# PowerKitPTH.net
KiCad netlist of a schematic drawn in EAGLE
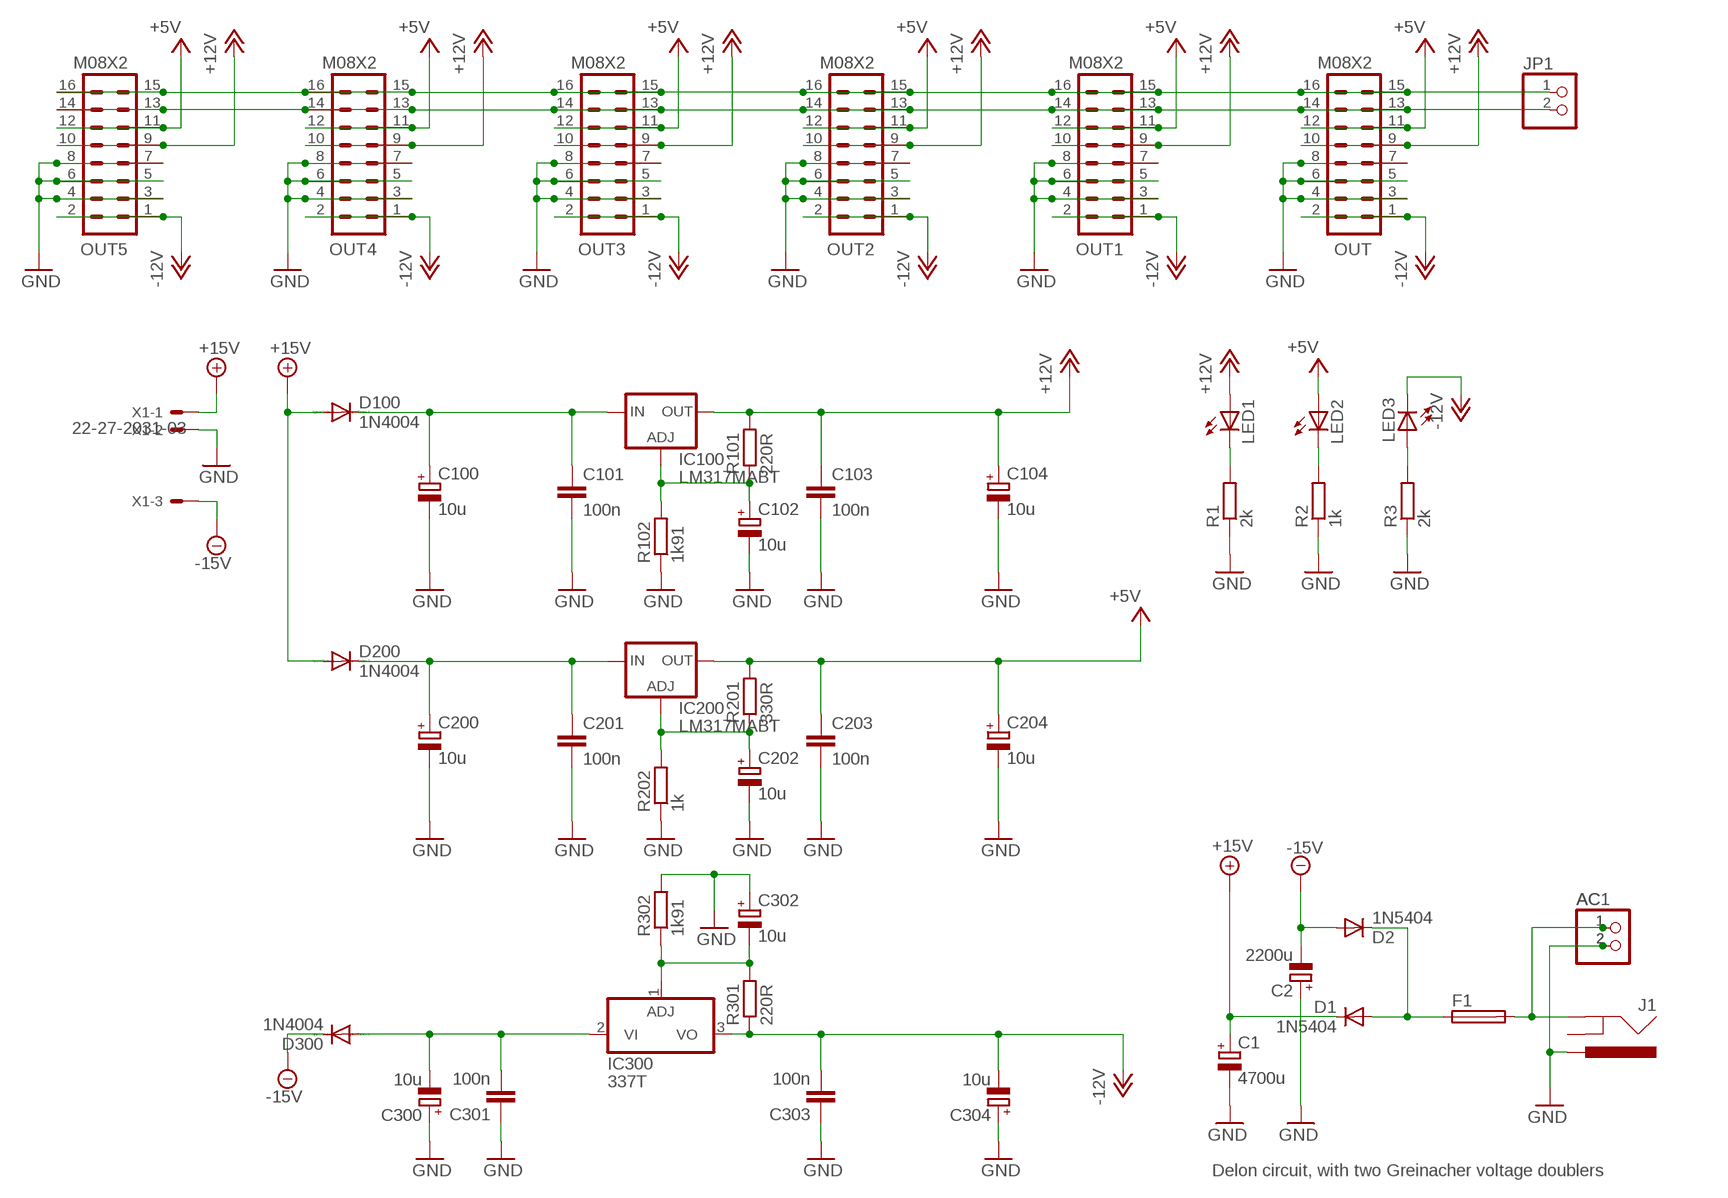
[diagram p0: schematic, sheet 1]

(export (version "E")
  (design (tool "Eeschema 10.0.6"))
  (components
    (comp (ref "AC")
      (value "PINHD-1X2")
      (footprint "eagle-import:1X02")
      (libsource (lib "eagle-import") (part "PINHD-1X2"))
    )
    (comp (ref "AC1")
      (value "PINHD-1X2")
      (footprint "eagle-import:1X02")
      (libsource (lib "eagle-import") (part "PINHD-1X2"))
    )
    (comp (ref "C1")
      (value "4700u")
      (footprint "eagle-import:E7,5-18")
      (libsource (lib "eagle-import") (part "resistor_CPOL-EUE7.5-18"))
    )
    (comp (ref "C2")
      (value "2200u")
      (footprint "eagle-import:E7,5-18")
      (libsource (lib "eagle-import") (part "resistor_CPOL-EUE7.5-18"))
    )
    (comp (ref "C100")
      (value "10u")
      (footprint "eagle-import:E2,5-6")
      (libsource (lib "eagle-import") (part "CPOL-EUE2.5-6"))
    )
    (comp (ref "C101")
      (value "100n")
      (footprint "eagle-import:C050-025X075")
      (libsource (lib "eagle-import") (part "C-EU050-025X075"))
    )
    (comp (ref "C102")
      (value "10u")
      (footprint "eagle-import:E2,5-6")
      (libsource (lib "eagle-import") (part "CPOL-EUE2.5-6"))
    )
    (comp (ref "C103")
      (value "100n")
      (footprint "eagle-import:C050-025X075")
      (libsource (lib "eagle-import") (part "C-EU050-025X075"))
    )
    (comp (ref "C104")
      (value "10u")
      (footprint "eagle-import:E2,5-6")
      (libsource (lib "eagle-import") (part "CPOL-EUE2.5-6"))
    )
    (comp (ref "C200")
      (value "10u")
      (footprint "eagle-import:E2,5-6")
      (libsource (lib "eagle-import") (part "CPOL-EUE2.5-6"))
    )
    (comp (ref "C201")
      (value "100n")
      (footprint "eagle-import:C050-025X075")
      (libsource (lib "eagle-import") (part "C-EU050-025X075"))
    )
    (comp (ref "C202")
      (value "10u")
      (footprint "eagle-import:E2,5-6")
      (libsource (lib "eagle-import") (part "CPOL-EUE2.5-6"))
    )
    (comp (ref "C203")
      (value "100n")
      (footprint "eagle-import:C050-025X075")
      (libsource (lib "eagle-import") (part "C-EU050-025X075"))
    )
    (comp (ref "C204")
      (value "10u")
      (footprint "eagle-import:E2,5-6")
      (libsource (lib "eagle-import") (part "CPOL-EUE2.5-6"))
    )
    (comp (ref "C300")
      (value "10u")
      (footprint "eagle-import:E2,5-6")
      (libsource (lib "eagle-import") (part "CPOL-EUE2.5-6"))
    )
    (comp (ref "C301")
      (value "100n")
      (footprint "eagle-import:C050-025X075")
      (libsource (lib "eagle-import") (part "C-EU050-025X075"))
    )
    (comp (ref "C302")
      (value "10u")
      (footprint "eagle-import:E2,5-6")
      (libsource (lib "eagle-import") (part "CPOL-EUE2.5-6"))
    )
    (comp (ref "C303")
      (value "100n")
      (footprint "eagle-import:C050-025X075")
      (libsource (lib "eagle-import") (part "C-EU050-025X075"))
    )
    (comp (ref "C304")
      (value "10u")
      (footprint "eagle-import:E2,5-6")
      (libsource (lib "eagle-import") (part "CPOL-EUE2.5-6"))
    )
    (comp (ref "D1")
      (value "1N5404")
      (footprint "eagle-import:DIODE-1N4001")
      (libsource (lib "eagle-import") (part "DIODE1N4001"))
    )
    (comp (ref "D2")
      (value "1N5404")
      (footprint "eagle-import:DIODE-1N4001")
      (libsource (lib "eagle-import") (part "DIODE1N4001"))
    )
    (comp (ref "D100")
      (value "1N4004")
      (footprint "eagle-import:DO41-10")
      (libsource (lib "eagle-import") (part "1N4004"))
    )
    (comp (ref "D200")
      (value "1N4004")
      (footprint "eagle-import:DO41-10")
      (libsource (lib "eagle-import") (part "1N4004"))
    )
    (comp (ref "D300")
      (value "1N4004")
      (footprint "eagle-import:DO41-10")
      (libsource (lib "eagle-import") (part "1N4004"))
    )
    (comp (ref "F1")
      (value "SH22,5")
      (footprint "eagle-import:SH22,5")
      (fields (field (name "MF") "SCHURTER") (field (name "MPN") "0031.8201"))
      (libsource (lib "eagle-import") (part "SH22,5"))
    )
    (comp (ref "IC100")
      (value "LM317MABT")
      (footprint "eagle-import:TO220L1")
      (libsource (lib "eagle-import") (part "LM317?MABT"))
    )
    (comp (ref "IC200")
      (value "LM317MABT")
      (footprint "eagle-import:TO220L1")
      (libsource (lib "eagle-import") (part "LM317?MABT"))
    )
    (comp (ref "IC300")
      (value "337T")
      (footprint "eagle-import:TO220H")
      (libsource (lib "eagle-import") (part "337T"))
    )
    (comp (ref "J1")
      (value "POWER_JACKPTH")
      (footprint "eagle-import:POWER_JACK_PTH")
      (libsource (lib "eagle-import") (part "POWER_JACKPTH"))
    )
    (comp (ref "JP1")
      (value "PINHD-1X2")
      (footprint "eagle-import:1X02")
      (libsource (lib "eagle-import") (part "PINHD-1X2"))
    )
    (comp (ref "LED1")
      (value "LED3MM")
      (footprint "eagle-import:LED3MM")
      (libsource (lib "eagle-import") (part "LED3MM"))
    )
    (comp (ref "LED2")
      (value "LED3MM")
      (footprint "eagle-import:LED3MM")
      (libsource (lib "eagle-import") (part "LED3MM"))
    )
    (comp (ref "LED3")
      (value "LED3MM")
      (footprint "eagle-import:LED3MM")
      (libsource (lib "eagle-import") (part "LED3MM"))
    )
    (comp (ref "OUT")
      (value "M08X2")
      (footprint "eagle-import:2X8")
      (libsource (lib "eagle-import") (part "M08X2"))
    )
    (comp (ref "OUT1")
      (value "M08X2")
      (footprint "eagle-import:2X8")
      (libsource (lib "eagle-import") (part "M08X2"))
    )
    (comp (ref "OUT2")
      (value "M08X2")
      (footprint "eagle-import:2X8")
      (libsource (lib "eagle-import") (part "M08X2"))
    )
    (comp (ref "OUT3")
      (value "M08X2")
      (footprint "eagle-import:2X8")
      (libsource (lib "eagle-import") (part "M08X2"))
    )
    (comp (ref "OUT4")
      (value "M08X2")
      (footprint "eagle-import:2X8")
      (libsource (lib "eagle-import") (part "M08X2"))
    )
    (comp (ref "OUT5")
      (value "M08X2")
      (footprint "eagle-import:2X8")
      (libsource (lib "eagle-import") (part "M08X2"))
    )
    (comp (ref "R1")
      (value "2k")
      (footprint "eagle-import:0204_7")
      (libsource (lib "eagle-import") (part "R-EU_0204/7"))
    )
    (comp (ref "R2")
      (value "1k")
      (footprint "eagle-import:0204_7")
      (libsource (lib "eagle-import") (part "R-EU_0204/7"))
    )
    (comp (ref "R3")
      (value "2k")
      (footprint "eagle-import:0204_7")
      (libsource (lib "eagle-import") (part "R-EU_0204/7"))
    )
    (comp (ref "R101")
      (value "220R")
      (footprint "eagle-import:0204_7")
      (libsource (lib "eagle-import") (part "R-EU_0204/7"))
    )
    (comp (ref "R102")
      (value "1k91")
      (footprint "eagle-import:0204_7")
      (libsource (lib "eagle-import") (part "R-EU_0204/7"))
    )
    (comp (ref "R201")
      (value "330R")
      (footprint "eagle-import:0204_7")
      (libsource (lib "eagle-import") (part "R-EU_0204/7"))
    )
    (comp (ref "R202")
      (value "1k")
      (footprint "eagle-import:0204_7")
      (libsource (lib "eagle-import") (part "R-EU_0204/7"))
    )
    (comp (ref "R301")
      (value "220R")
      (footprint "eagle-import:0204_7")
      (libsource (lib "eagle-import") (part "R-EU_0204/7"))
    )
    (comp (ref "R302")
      (value "1k91")
      (footprint "eagle-import:0204_7")
      (libsource (lib "eagle-import") (part "R-EU_0204/7"))
    )
    (comp (ref "X1")
      (value "22-27-2031-03")
      (footprint "eagle-import:6410-03")
      (libsource (lib "eagle-import") (part "22-?-0327-2031"))
    )
  )
  (nets
    (net (code "1") (name "+5V") (class "Default")
      (node (ref "C203") (pin "1") (pinfunction "1_1") (pintype "passive"))
      (node (ref "C204") (pin "+") (pinfunction "+_+") (pintype "passive"))
      (node (ref "IC200") (pin "2") (pinfunction "OUT_2") (pintype "passive"))
      (node (ref "LED2") (pin "A") (pinfunction "A_A") (pintype "passive"))
      (node (ref "OUT") (pin "11") (pinfunction "11_11") (pintype "passive"))
      (node (ref "OUT") (pin "12") (pinfunction "12_12") (pintype "passive"))
      (node (ref "OUT1") (pin "11") (pinfunction "11_11") (pintype "passive"))
      (node (ref "OUT1") (pin "12") (pinfunction "12_12") (pintype "passive"))
      (node (ref "OUT2") (pin "11") (pinfunction "11_11") (pintype "passive"))
      (node (ref "OUT2") (pin "12") (pinfunction "12_12") (pintype "passive"))
      (node (ref "OUT3") (pin "11") (pinfunction "11_11") (pintype "passive"))
      (node (ref "OUT3") (pin "12") (pinfunction "12_12") (pintype "passive"))
      (node (ref "OUT4") (pin "11") (pinfunction "11_11") (pintype "passive"))
      (node (ref "OUT4") (pin "12") (pinfunction "12_12") (pintype "passive"))
      (node (ref "OUT5") (pin "11") (pinfunction "11_11") (pintype "passive"))
      (node (ref "OUT5") (pin "12") (pinfunction "12_12") (pintype "passive"))
      (node (ref "R201") (pin "2") (pinfunction "2_2") (pintype "passive"))
    )
    (net (code "2") (name "+12V") (class "Default")
      (node (ref "C103") (pin "1") (pinfunction "1_1") (pintype "passive"))
      (node (ref "C104") (pin "+") (pinfunction "+_+") (pintype "passive"))
      (node (ref "IC100") (pin "2") (pinfunction "OUT_2") (pintype "passive"))
      (node (ref "LED1") (pin "A") (pinfunction "A_A") (pintype "passive"))
      (node (ref "OUT") (pin "10") (pinfunction "10_10") (pintype "passive"))
      (node (ref "OUT") (pin "9") (pinfunction "9_9") (pintype "passive"))
      (node (ref "OUT1") (pin "10") (pinfunction "10_10") (pintype "passive"))
      (node (ref "OUT1") (pin "9") (pinfunction "9_9") (pintype "passive"))
      (node (ref "OUT2") (pin "10") (pinfunction "10_10") (pintype "passive"))
      (node (ref "OUT2") (pin "9") (pinfunction "9_9") (pintype "passive"))
      (node (ref "OUT3") (pin "10") (pinfunction "10_10") (pintype "passive"))
      (node (ref "OUT3") (pin "9") (pinfunction "9_9") (pintype "passive"))
      (node (ref "OUT4") (pin "10") (pinfunction "10_10") (pintype "passive"))
      (node (ref "OUT4") (pin "9") (pinfunction "9_9") (pintype "passive"))
      (node (ref "OUT5") (pin "10") (pinfunction "10_10") (pintype "passive"))
      (node (ref "OUT5") (pin "9") (pinfunction "9_9") (pintype "passive"))
      (node (ref "R101") (pin "2") (pinfunction "2_2") (pintype "passive"))
    )
    (net (code "3") (name "+15V") (class "Default")
      (node (ref "C1") (pin "+") (pinfunction "+_+") (pintype "passive"))
      (node (ref "D1") (pin "C") (pinfunction "C_C") (pintype "passive"))
      (node (ref "D100") (pin "A") (pinfunction "A_A") (pintype "passive"))
      (node (ref "D200") (pin "A") (pinfunction "A_A") (pintype "passive"))
      (node (ref "X1") (pin "1") (pinfunction "S_1") (pintype "passive"))
    )
    (net (code "4") (name "-12V") (class "Default")
      (node (ref "C303") (pin "2") (pinfunction "2_2") (pintype "passive"))
      (node (ref "C304") (pin "-") (pinfunction "-_-") (pintype "passive"))
      (node (ref "IC300") (pin "3") (pinfunction "VO_3") (pintype "passive"))
      (node (ref "LED3") (pin "K") (pinfunction "C_K") (pintype "passive"))
      (node (ref "OUT") (pin "1") (pinfunction "1_1") (pintype "passive"))
      (node (ref "OUT") (pin "2") (pinfunction "2_2") (pintype "passive"))
      (node (ref "OUT1") (pin "1") (pinfunction "1_1") (pintype "passive"))
      (node (ref "OUT1") (pin "2") (pinfunction "2_2") (pintype "passive"))
      (node (ref "OUT2") (pin "1") (pinfunction "1_1") (pintype "passive"))
      (node (ref "OUT2") (pin "2") (pinfunction "2_2") (pintype "passive"))
      (node (ref "OUT3") (pin "1") (pinfunction "1_1") (pintype "passive"))
      (node (ref "OUT3") (pin "2") (pinfunction "2_2") (pintype "passive"))
      (node (ref "OUT4") (pin "1") (pinfunction "1_1") (pintype "passive"))
      (node (ref "OUT4") (pin "2") (pinfunction "2_2") (pintype "passive"))
      (node (ref "OUT5") (pin "1") (pinfunction "1_1") (pintype "passive"))
      (node (ref "OUT5") (pin "2") (pinfunction "2_2") (pintype "passive"))
      (node (ref "R301") (pin "1") (pinfunction "1_1") (pintype "passive"))
    )
    (net (code "5") (name "-15V") (class "Default")
      (node (ref "C2") (pin "-") (pinfunction "-_-") (pintype "passive"))
      (node (ref "D2") (pin "A") (pinfunction "A_A") (pintype "passive"))
      (node (ref "D300") (pin "C") (pinfunction "C_C") (pintype "passive"))
      (node (ref "X1") (pin "3") (pinfunction "S_3") (pintype "passive"))
    )
    (net (code "6") (name "GND") (class "Default")
      (node (ref "AC") (pin "2") (pinfunction "2_2") (pintype "passive"))
      (node (ref "AC1") (pin "2") (pinfunction "2_2") (pintype "passive"))
      (node (ref "C1") (pin "-") (pinfunction "-_-") (pintype "passive"))
      (node (ref "C100") (pin "-") (pinfunction "-_-") (pintype "passive"))
      (node (ref "C101") (pin "2") (pinfunction "2_2") (pintype "passive"))
      (node (ref "C102") (pin "-") (pinfunction "-_-") (pintype "passive"))
      (node (ref "C103") (pin "2") (pinfunction "2_2") (pintype "passive"))
      (node (ref "C104") (pin "-") (pinfunction "-_-") (pintype "passive"))
      (node (ref "C2") (pin "+") (pinfunction "+_+") (pintype "passive"))
      (node (ref "C200") (pin "-") (pinfunction "-_-") (pintype "passive"))
      (node (ref "C201") (pin "2") (pinfunction "2_2") (pintype "passive"))
      (node (ref "C202") (pin "-") (pinfunction "-_-") (pintype "passive"))
      (node (ref "C203") (pin "2") (pinfunction "2_2") (pintype "passive"))
      (node (ref "C204") (pin "-") (pinfunction "-_-") (pintype "passive"))
      (node (ref "C300") (pin "+") (pinfunction "+_+") (pintype "passive"))
      (node (ref "C301") (pin "1") (pinfunction "1_1") (pintype "passive"))
      (node (ref "C302") (pin "+") (pinfunction "+_+") (pintype "passive"))
      (node (ref "C303") (pin "1") (pinfunction "1_1") (pintype "passive"))
      (node (ref "C304") (pin "+") (pinfunction "+_+") (pintype "passive"))
      (node (ref "J1") (pin "PWR") (pinfunction "PWR_PWR") (pintype "bidirectional"))
      (node (ref "OUT") (pin "3") (pinfunction "3_3") (pintype "passive"))
      (node (ref "OUT") (pin "4") (pinfunction "4_4") (pintype "passive"))
      (node (ref "OUT") (pin "5") (pinfunction "5_5") (pintype "passive"))
      (node (ref "OUT") (pin "6") (pinfunction "6_6") (pintype "passive"))
      (node (ref "OUT") (pin "7") (pinfunction "7_7") (pintype "passive"))
      (node (ref "OUT") (pin "8") (pinfunction "8_8") (pintype "passive"))
      (node (ref "OUT1") (pin "3") (pinfunction "3_3") (pintype "passive"))
      (node (ref "OUT1") (pin "4") (pinfunction "4_4") (pintype "passive"))
      (node (ref "OUT1") (pin "5") (pinfunction "5_5") (pintype "passive"))
      (node (ref "OUT1") (pin "6") (pinfunction "6_6") (pintype "passive"))
      (node (ref "OUT1") (pin "7") (pinfunction "7_7") (pintype "passive"))
      (node (ref "OUT1") (pin "8") (pinfunction "8_8") (pintype "passive"))
      (node (ref "OUT2") (pin "3") (pinfunction "3_3") (pintype "passive"))
      (node (ref "OUT2") (pin "4") (pinfunction "4_4") (pintype "passive"))
      (node (ref "OUT2") (pin "5") (pinfunction "5_5") (pintype "passive"))
      (node (ref "OUT2") (pin "6") (pinfunction "6_6") (pintype "passive"))
      (node (ref "OUT2") (pin "7") (pinfunction "7_7") (pintype "passive"))
      (node (ref "OUT2") (pin "8") (pinfunction "8_8") (pintype "passive"))
      (node (ref "OUT3") (pin "3") (pinfunction "3_3") (pintype "passive"))
      (node (ref "OUT3") (pin "4") (pinfunction "4_4") (pintype "passive"))
      (node (ref "OUT3") (pin "5") (pinfunction "5_5") (pintype "passive"))
      (node (ref "OUT3") (pin "6") (pinfunction "6_6") (pintype "passive"))
      (node (ref "OUT3") (pin "7") (pinfunction "7_7") (pintype "passive"))
      (node (ref "OUT3") (pin "8") (pinfunction "8_8") (pintype "passive"))
      (node (ref "OUT4") (pin "3") (pinfunction "3_3") (pintype "passive"))
      (node (ref "OUT4") (pin "4") (pinfunction "4_4") (pintype "passive"))
      (node (ref "OUT4") (pin "5") (pinfunction "5_5") (pintype "passive"))
      (node (ref "OUT4") (pin "6") (pinfunction "6_6") (pintype "passive"))
      (node (ref "OUT4") (pin "7") (pinfunction "7_7") (pintype "passive"))
      (node (ref "OUT4") (pin "8") (pinfunction "8_8") (pintype "passive"))
      (node (ref "OUT5") (pin "3") (pinfunction "3_3") (pintype "passive"))
      (node (ref "OUT5") (pin "4") (pinfunction "4_4") (pintype "passive"))
      (node (ref "OUT5") (pin "5") (pinfunction "5_5") (pintype "passive"))
      (node (ref "OUT5") (pin "6") (pinfunction "6_6") (pintype "passive"))
      (node (ref "OUT5") (pin "7") (pinfunction "7_7") (pintype "passive"))
      (node (ref "OUT5") (pin "8") (pinfunction "8_8") (pintype "passive"))
      (node (ref "R1") (pin "1") (pinfunction "1_1") (pintype "passive"))
      (node (ref "R102") (pin "1") (pinfunction "1_1") (pintype "passive"))
      (node (ref "R2") (pin "1") (pinfunction "1_1") (pintype "passive"))
      (node (ref "R202") (pin "1") (pinfunction "1_1") (pintype "passive"))
      (node (ref "R3") (pin "1") (pinfunction "1_1") (pintype "passive"))
      (node (ref "R302") (pin "2") (pinfunction "2_2") (pintype "passive"))
      (node (ref "X1") (pin "2") (pinfunction "S_2") (pintype "passive"))
    )
    (net (code "7") (name "Net-(AC-Pad1)") (class "Default")
      (node (ref "AC") (pin "1") (pinfunction "1_1") (pintype "passive"))
      (node (ref "AC1") (pin "1") (pinfunction "1_1") (pintype "passive"))
      (node (ref "F1") (pin "2") (pinfunction "2_2") (pintype "passive"))
      (node (ref "J1") (pin "GND") (pinfunction "GND_GND") (pintype "bidirectional"))
    )
    (net (code "8") (name "Net-(D1-PadA)") (class "Default")
      (node (ref "D1") (pin "A") (pinfunction "A_A") (pintype "passive"))
      (node (ref "D2") (pin "C") (pinfunction "C_C") (pintype "passive"))
      (node (ref "F1") (pin "1") (pinfunction "1_1") (pintype "passive"))
    )
    (net (code "9") (name "Net-(IC100-ADJ)") (class "Default")
      (node (ref "C102") (pin "+") (pinfunction "+_+") (pintype "passive"))
      (node (ref "IC100") (pin "1") (pinfunction "ADJ_1") (pintype "input"))
      (node (ref "R101") (pin "1") (pinfunction "1_1") (pintype "passive"))
      (node (ref "R102") (pin "2") (pinfunction "2_2") (pintype "passive"))
    )
    (net (code "10") (name "Net-(IC100-IN)") (class "Default")
      (node (ref "C100") (pin "+") (pinfunction "+_+") (pintype "passive"))
      (node (ref "C101") (pin "1") (pinfunction "1_1") (pintype "passive"))
      (node (ref "D100") (pin "C") (pinfunction "C_C") (pintype "passive"))
      (node (ref "IC100") (pin "3") (pinfunction "IN_3") (pintype "input"))
    )
    (net (code "11") (name "Net-(IC200-ADJ)") (class "Default")
      (node (ref "C202") (pin "+") (pinfunction "+_+") (pintype "passive"))
      (node (ref "IC200") (pin "1") (pinfunction "ADJ_1") (pintype "input"))
      (node (ref "R201") (pin "1") (pinfunction "1_1") (pintype "passive"))
      (node (ref "R202") (pin "2") (pinfunction "2_2") (pintype "passive"))
    )
    (net (code "12") (name "Net-(IC200-IN)") (class "Default")
      (node (ref "C200") (pin "+") (pinfunction "+_+") (pintype "passive"))
      (node (ref "C201") (pin "1") (pinfunction "1_1") (pintype "passive"))
      (node (ref "D200") (pin "C") (pinfunction "C_C") (pintype "passive"))
      (node (ref "IC200") (pin "3") (pinfunction "IN_3") (pintype "input"))
    )
    (net (code "13") (name "Net-(IC300-ADJ)") (class "Default")
      (node (ref "C302") (pin "-") (pinfunction "-_-") (pintype "passive"))
      (node (ref "IC300") (pin "1") (pinfunction "ADJ_1") (pintype "input"))
      (node (ref "R301") (pin "2") (pinfunction "2_2") (pintype "passive"))
      (node (ref "R302") (pin "1") (pinfunction "1_1") (pintype "passive"))
    )
    (net (code "14") (name "Net-(IC300-VI)") (class "Default")
      (node (ref "C300") (pin "-") (pinfunction "-_-") (pintype "passive"))
      (node (ref "C301") (pin "2") (pinfunction "2_2") (pintype "passive"))
      (node (ref "D300") (pin "A") (pinfunction "A_A") (pintype "passive"))
      (node (ref "IC300") (pin "2") (pinfunction "VI_2") (pintype "input"))
    )
    (net (code "15") (name "Net-(JP1-Pad1)") (class "Default")
      (node (ref "JP1") (pin "1") (pinfunction "1_1") (pintype "passive"))
      (node (ref "OUT") (pin "15") (pinfunction "15_15") (pintype "passive"))
      (node (ref "OUT") (pin "16") (pinfunction "16_16") (pintype "passive"))
      (node (ref "OUT1") (pin "15") (pinfunction "15_15") (pintype "passive"))
      (node (ref "OUT1") (pin "16") (pinfunction "16_16") (pintype "passive"))
      (node (ref "OUT2") (pin "15") (pinfunction "15_15") (pintype "passive"))
      (node (ref "OUT2") (pin "16") (pinfunction "16_16") (pintype "passive"))
      (node (ref "OUT3") (pin "15") (pinfunction "15_15") (pintype "passive"))
      (node (ref "OUT3") (pin "16") (pinfunction "16_16") (pintype "passive"))
      (node (ref "OUT4") (pin "15") (pinfunction "15_15") (pintype "passive"))
      (node (ref "OUT4") (pin "16") (pinfunction "16_16") (pintype "passive"))
      (node (ref "OUT5") (pin "15") (pinfunction "15_15") (pintype "passive"))
      (node (ref "OUT5") (pin "16") (pinfunction "16_16") (pintype "passive"))
    )
    (net (code "16") (name "Net-(JP1-Pad2)") (class "Default")
      (node (ref "JP1") (pin "2") (pinfunction "2_2") (pintype "passive"))
      (node (ref "OUT") (pin "13") (pinfunction "13_13") (pintype "passive"))
      (node (ref "OUT") (pin "14") (pinfunction "14_14") (pintype "passive"))
      (node (ref "OUT1") (pin "13") (pinfunction "13_13") (pintype "passive"))
      (node (ref "OUT1") (pin "14") (pinfunction "14_14") (pintype "passive"))
      (node (ref "OUT2") (pin "13") (pinfunction "13_13") (pintype "passive"))
      (node (ref "OUT2") (pin "14") (pinfunction "14_14") (pintype "passive"))
      (node (ref "OUT3") (pin "13") (pinfunction "13_13") (pintype "passive"))
      (node (ref "OUT3") (pin "14") (pinfunction "14_14") (pintype "passive"))
      (node (ref "OUT4") (pin "13") (pinfunction "13_13") (pintype "passive"))
      (node (ref "OUT4") (pin "14") (pinfunction "14_14") (pintype "passive"))
      (node (ref "OUT5") (pin "13") (pinfunction "13_13") (pintype "passive"))
      (node (ref "OUT5") (pin "14") (pinfunction "14_14") (pintype "passive"))
    )
    (net (code "17") (name "Net-(LED1-C)") (class "Default")
      (node (ref "LED1") (pin "K") (pinfunction "C_K") (pintype "passive"))
      (node (ref "R1") (pin "2") (pinfunction "2_2") (pintype "passive"))
    )
    (net (code "18") (name "Net-(LED2-C)") (class "Default")
      (node (ref "LED2") (pin "K") (pinfunction "C_K") (pintype "passive"))
      (node (ref "R2") (pin "2") (pinfunction "2_2") (pintype "passive"))
    )
    (net (code "19") (name "Net-(LED3-PadA)") (class "Default")
      (node (ref "LED3") (pin "A") (pinfunction "A_A") (pintype "passive"))
      (node (ref "R3") (pin "2") (pinfunction "2_2") (pintype "passive"))
    )
    (net (code "20") (name "unconnected-(J1-PadGNDBREAK)") (class "Default")
      (node (ref "J1") (pin "GNDBREAK") (pinfunction "GNDBREAK_GNDBREAK") (pintype "bidirectional"))
    )
  )
)
